# SolderIronOut.net
KiCad netlist of a schematic drawn in Altium Designer
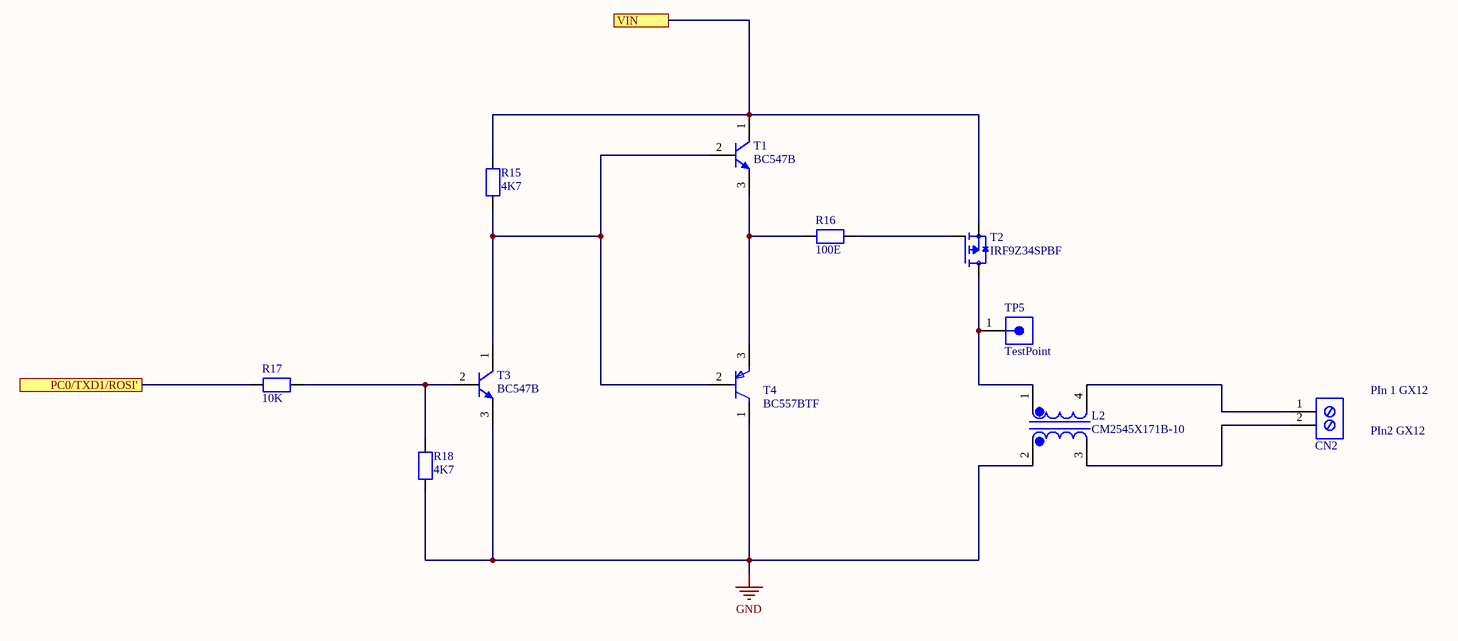
[diagram p0: SolderIronOut.SchDoc]

(export (version "E")
  (design (tool "Eeschema 10.0.6"))
  (components
    (comp (ref "CN2")
      (value "Printkroonsteen 2 POL")
      (footprint "Printkroonsteen 2pin")
      (description "Printkroonsteen 2 PO L1716020000")
      (fields
        (field (name "MANUFACTURER_PART_NUMBER") "1716020000")
        (field (name "MOUSER PART NUMBER") "470-1716020000")
      )
      (libsource (lib "SolderStation") (part "printkroonsteen 1 X 2"))
    )
    (comp (ref "L2")
      (value "CM2545X171B-10")
      (footprint "XFMR_CM2545X171B-10")
      (description "2 Line Common Mode Choke Through Hole 170 Ohms @ 100 MHz 10A DCR 10mOhm")
      (fields (field (name "MF") "Laird"))
      (libsource (lib "SolderStation") (part "CM2545X171B-10"))
    )
    (comp (ref "R15")
      (value "4K7")
      (footprint "RESC2012X50N")
      (fields (field (name "MANUFACTURER") "Vishay Dale") (field (name "PART NUMBER") "CRCW08050000Z0EA"))
      (libsource (lib "SolderStation") (part "resistor 0805"))
    )
    (comp (ref "R16")
      (value "100E")
      (footprint "RESC2012X50N")
      (fields (field (name "MANUFACTURER") "Vishay Dale") (field (name "PART NUMBER") "CRCW08050000Z0EA"))
      (libsource (lib "SolderStation") (part "resistor 0805"))
    )
    (comp (ref "R17")
      (value "10K")
      (footprint "RESC2012X50N")
      (fields (field (name "MANUFACTURER") "Vishay Dale") (field (name "PART NUMBER") "CRCW08050000Z0EA"))
      (libsource (lib "SolderStation") (part "resistor 0805"))
    )
    (comp (ref "R18")
      (value "4K7")
      (footprint "RESC2012X50N")
      (fields (field (name "MANUFACTURER") "Vishay Dale") (field (name "PART NUMBER") "CRCW08050000Z0EA"))
      (libsource (lib "SolderStation") (part "resistor 0805"))
    )
    (comp (ref "T1")
      (value "BC547B")
      (footprint "ONSC-TO-92-3-29-11")
      (description "Amplifier Transistor, NPN Silicon, 3-Pin TO-92, Bulk Box CMP-1048-01467-1")
      (fields (field (name "MANUFACTURER") "On Semiconductor"))
      (libsource (lib "SolderStation") (part "Transistor NPN BC547B THT"))
    )
    (comp (ref "T2")
      (value "IRF9Z34SPBF")
      (footprint "TO254P1521X483-4N")
      (description "P-Channel 60V 18A _Tc_ 3.7W _Ta_, 88W _Tc_ Surface Mount D2PAK")
      (fields (field (name "MF") "Vishay"))
      (libsource (lib "SolderStation") (part "IRF9Z34SPBF"))
    )
    (comp (ref "T3")
      (value "BC547B")
      (footprint "ONSC-TO-92-3-29-11")
      (description "Amplifier Transistor, NPN Silicon, 3-Pin TO-92, Bulk Box CMP-1048-01467-1")
      (fields (field (name "MANUFACTURER") "On Semiconductor"))
      (libsource (lib "SolderStation") (part "Transistor NPN BC547B THT"))
    )
    (comp (ref "T4")
      (value "BC557BTF")
      (footprint "ONSC-TO-92-3-29-11")
      (libsource (lib "SolderStation") (part "Transistor PNP BC557 THT"))
    )
    (comp (ref "TP5")
      (value "TestPoint")
      (footprint "61300111121")
      (libsource (lib "SolderStation") (part "TestPoint"))
    )
  )
  (nets
    (net (code "1") (name "/PC0{slash}TXD1{slash}ROSI'") (class "Default")
      (node (ref "R17") (pin "2") (pinfunction "2_2") (pintype "passive"))
    )
    (net (code "2") (name "/VIN") (class "Default")
      (node (ref "R15") (pin "2") (pinfunction "2_2") (pintype "passive"))
      (node (ref "T1") (pin "1") (pinfunction "C_1") (pintype "passive"))
      (node (ref "T2") (pin "3") (pinfunction "S_3") (pintype "passive"))
    )
    (net (code "3") (name "GND") (class "Default")
      (node (ref "L2") (pin "2") (pinfunction "2_2") (pintype "passive"))
      (node (ref "R18") (pin "1") (pinfunction "1_1") (pintype "passive"))
      (node (ref "T3") (pin "3") (pinfunction "E_3") (pintype "passive"))
      (node (ref "T4") (pin "1") (pinfunction "C_1") (pintype "passive"))
    )
    (net (code "4") (name "Net-(CN2-Pad1)") (class "Default")
      (node (ref "CN2") (pin "1") (pinfunction "1_1") (pintype "passive"))
      (node (ref "L2") (pin "4") (pinfunction "4_4") (pintype "passive"))
    )
    (net (code "5") (name "Net-(CN2-Pad2)") (class "Default")
      (node (ref "CN2") (pin "2") (pinfunction "2_2") (pintype "passive"))
      (node (ref "L2") (pin "3") (pinfunction "3_3") (pintype "passive"))
    )
    (net (code "6") (name "Net-(T1-B)") (class "Default")
      (node (ref "R15") (pin "1") (pinfunction "1_1") (pintype "passive"))
      (node (ref "T1") (pin "2") (pinfunction "B_2") (pintype "passive"))
      (node (ref "T3") (pin "1") (pinfunction "C_1") (pintype "passive"))
      (node (ref "T4") (pin "2") (pinfunction "B_2") (pintype "passive"))
    )
    (net (code "7") (name "Net-(T1-E)") (class "Default")
      (node (ref "R16") (pin "2") (pinfunction "2_2") (pintype "passive"))
      (node (ref "T1") (pin "3") (pinfunction "E_3") (pintype "passive"))
      (node (ref "T4") (pin "3") (pinfunction "E_3") (pintype "passive"))
    )
    (net (code "8") (name "Net-(T2-D)") (class "Default")
      (node (ref "L2") (pin "1") (pinfunction "1_1") (pintype "passive"))
      (node (ref "T2") (pin "4") (pinfunction "D_4") (pintype "passive"))
      (node (ref "TP5") (pin "1") (pinfunction "1_1") (pintype "passive"))
    )
    (net (code "9") (name "Net-(T2-G)") (class "Default")
      (node (ref "R16") (pin "1") (pinfunction "1_1") (pintype "passive"))
      (node (ref "T2") (pin "1") (pinfunction "G_1") (pintype "passive"))
    )
    (net (code "10") (name "Net-(T3-B)") (class "Default")
      (node (ref "R17") (pin "1") (pinfunction "1_1") (pintype "passive"))
      (node (ref "R18") (pin "2") (pinfunction "2_2") (pintype "passive"))
      (node (ref "T3") (pin "2") (pinfunction "B_2") (pintype "passive"))
    )
  )
)
